# Power.net
KiCad netlist of a schematic drawn in Altium Designer
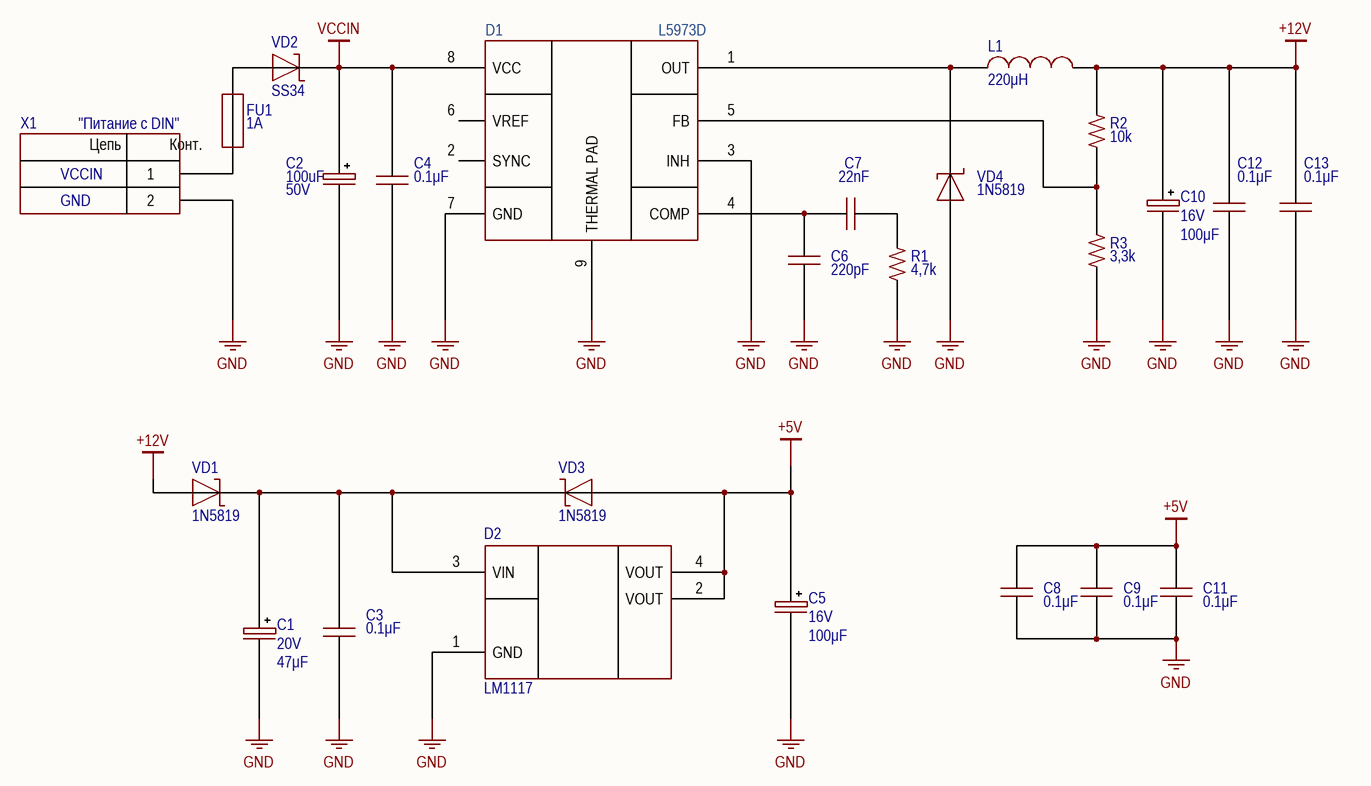
[diagram p0: Power.SchDoc]

(export (version "E")
  (design (tool "Eeschema 10.0.6"))
  (components
    (comp (ref "C1")
      (value "~")
      (footprint "Standart_Case:CAP: TANTAL-D")
      (fields (field (name "НАПРЯЖЕНИЕ") "20V") (field (name "ЗНАЧЕНИЕ") "47μF"))
      (libsource (lib "Capacitor") (part "Танталы SMD"))
    )
    (comp (ref "C2")
      (value "100uF")
      (footprint "Custom_Case:CAP: SMD D8A6.9")
      (fields
        (field (name "MANUFACTURER") "Capxon International Elec")
        (field (name "PARTNUMBER") "TH102M025I200ECAB")
        (field (name "VOLTAGE") "50V")
      )
      (libsource (lib "Capacitor") (part "Aluminium"))
    )
    (comp (ref "C3")
      (value "0.1μF")
      (footprint "Standart_Case:CAP: 0805")
      (fields
        (field (name "MANUFACTURER") "Murata Electronics")
        (field (name "PARTNUMBER") "GRM21BR71H104KA01L")
        (field (name "VALUEMANUFACTURERPARTNUMBER") "Керамический конденсатор, 0.1μF, X7R, ±10%, 16V, 0805, -55...+125°C")
      )
      (libsource (lib "Capacitor") (part "Ceramic_0805"))
    )
    (comp (ref "C4")
      (value "0.1μF")
      (footprint "Standart_Case:CAP: 0805")
      (fields
        (field (name "MANUFACTURER") "Murata Electronics")
        (field (name "PARTNUMBER") "GRM21BR71H104KA01L")
        (field (name "VALUEMANUFACTURERPARTNUMBER") "Керамический конденсатор, 0.1μF, X7R, ±10%, 50V, 0805, -55...+125°C")
      )
      (libsource (lib "Capacitor") (part "Ceramic_0805"))
    )
    (comp (ref "C5")
      (value "~")
      (footprint "Standart_Case:CAP: TANTAL-D")
      (fields (field (name "НАПРЯЖЕНИЕ") "16V") (field (name "ЗНАЧЕНИЕ") "100μF"))
      (libsource (lib "Capacitor") (part "Танталы SMD"))
    )
    (comp (ref "C6")
      (value "220pF")
      (footprint "Standart_Case:CAP: 0805")
      (fields
        (field (name "MANUFACTURER") "Murata Electronics")
        (field (name "PARTNUMBER") "GCJ21BR71H224KA01L")
        (field (name "VALUEMANUFACTURERPARTNUMBER") "Керамический конденсатор, 220pF, X7R, ±10%, 16V, 0805, -55...+125°C")
      )
      (libsource (lib "Capacitor") (part "Ceramic_0805"))
    )
    (comp (ref "C7")
      (value "22nF")
      (footprint "Standart_Case:CAP: 0805")
      (fields
        (field (name "MANUFACTURER") "Murata Electronics")
        (field (name "PARTNUMBER") "GCM216R71H223KA37D")
        (field (name "VALUEMANUFACTURERPARTNUMBER") "Керамический конденсатор, 22nF, X7R, ±10%, 16V, 0805, -55...+125°C")
      )
      (libsource (lib "Capacitor") (part "Ceramic_0805"))
    )
    (comp (ref "C8")
      (value "0.1μF")
      (footprint "Standart_Case:CAP: 0805")
      (fields
        (field (name "MANUFACTURER") "Murata Electronics")
        (field (name "PARTNUMBER") "GRM21BR71H104KA01L")
        (field (name "VALUEMANUFACTURERPARTNUMBER") "Керамический конденсатор, 0.1μF, X7R, ±10%, 16V, 0805, -55...+125°C")
      )
      (libsource (lib "Capacitor") (part "Ceramic_0805"))
    )
    (comp (ref "C9")
      (value "0.1μF")
      (footprint "Standart_Case:CAP: 0805")
      (fields
        (field (name "MANUFACTURER") "Murata Electronics")
        (field (name "PARTNUMBER") "GRM21BR71H104KA01L")
        (field (name "VALUEMANUFACTURERPARTNUMBER") "Керамический конденсатор, 0.1μF, X7R, ±10%, 16V, 0805, -55...+125°C")
      )
      (libsource (lib "Capacitor") (part "Ceramic_0805"))
    )
    (comp (ref "C10")
      (value "~")
      (footprint "Standart_Case:CAP: TANTAL-D")
      (fields (field (name "НАПРЯЖЕНИЕ") "16V") (field (name "ЗНАЧЕНИЕ") "100μF"))
      (libsource (lib "Capacitor") (part "Танталы SMD"))
    )
    (comp (ref "C11")
      (value "0.1μF")
      (footprint "Standart_Case:CAP: 0805")
      (fields
        (field (name "MANUFACTURER") "Murata Electronics")
        (field (name "PARTNUMBER") "GRM21BR71H104KA01L")
        (field (name "VALUEMANUFACTURERPARTNUMBER") "Керамический конденсатор, 0.1μF, X7R, ±10%, 16V, 0805, -55...+125°C")
      )
      (libsource (lib "Capacitor") (part "Ceramic_0805"))
    )
    (comp (ref "C12")
      (value "0.1μF")
      (footprint "Standart_Case:CAP: 0805")
      (fields
        (field (name "MANUFACTURER") "Murata Electronics")
        (field (name "PARTNUMBER") "GRM21BR71H104KA01L")
        (field (name "VALUEMANUFACTURERPARTNUMBER") "Керамический конденсатор, 0.1μF, X7R, ±10%, 16V, 0805, -55...+125°C")
      )
      (libsource (lib "Capacitor") (part "Ceramic_0805"))
    )
    (comp (ref "C13")
      (value "0.1μF")
      (footprint "Standart_Case:CAP: 0805")
      (fields
        (field (name "MANUFACTURER") "Murata Electronics")
        (field (name "PARTNUMBER") "GRM21BR71H104KA01L")
        (field (name "VALUEMANUFACTURERPARTNUMBER") "Керамический конденсатор, 0.1μF, X7R, ±10%, 16V, 0805, -55...+125°C")
      )
      (libsource (lib "Capacitor") (part "Ceramic_0805"))
    )
    (comp (ref "D1")
      (value "L5973D")
      (footprint "Standart_Case:HSOIC-DDA-8")
      (description "Импульсный понижающий регулятор напряжения")
      (fields (field (name "MANUFACTURER") "STMicroelectronics") (field (name "PARTNUMBER") "L5973D013TR"))
      (libsource (lib "IC_Power_Supply") (part "L5973D"))
    )
    (comp (ref "D2")
      (value "~")
      (footprint "Standart_Case:SOT223")
      (description "Линейный регулятор с низким падением напряжения")
      (fields (field (name "MANUFACTURER") "STMicroelectronics") (field (name "PARTNUMBER") "LM1117"))
      (libsource (lib "IC_Power_Supply") (part "LM1117"))
    )
    (comp (ref "FU1")
      (value "~")
      (footprint "Standart_case:FUSE: 1812")
      (fields
        (field (name "MANUFACTURER") "Littelfuse")
        (field (name "VALUEMANUFACTURERPARTNUMBER") "Предохранитель SMD, 250VAC, 1A, 1206, ")
        (field (name "PARTNUMBER") "0468001.NR")
        (field (name "MAXCURRENT") "1A")
      )
      (libsource (lib "Electromechanics") (part "Fuse"))
    )
    (comp (ref "L1")
      (value "220μH")
      (footprint "Custom_Case:IND: CD54")
      (fields
        (field (name "MANUFACTURER") "YJYCOIN")
        (field (name "PARTNUMBER") "CD54YP0504-221M")
        (field (name "VALUEMANUFACTURERPARTNUMBER") "Fixed inductor, 220μH, ±20%, CD54, 1.44A, -40...+100°C")
      )
      (libsource (lib "Inductor") (part "Inductor_CD54"))
    )
    (comp (ref "R1")
      (value "4,7k")
      (footprint "Standart_Case:RES: 0805")
      (fields
        (field (name "MANUFACTURER") "Vishay Intertech")
        (field (name "PARTNUMBER") "CRCW08054K70JNEA")
        (field (name "VALUEMANUFACTURERPARTNUMBER") "Резистор SMD, 4,7k, ±1%, 0805, 0.125W, -55...+125°C")
      )
      (libsource (lib "Resistor") (part "Resistor_0805_ieee"))
    )
    (comp (ref "R2")
      (value "10k")
      (footprint "Standart_Case:RES: 0805")
      (fields
        (field (name "MANUFACTURER") "Vishay Intertech")
        (field (name "PARTNUMBER") "CRCW080510K0FKEA")
        (field (name "VALUEMANUFACTURERPARTNUMBER") "Резистор SMD, 10k, ±1%, 0805, 0.125W, -55...+125°C")
      )
      (libsource (lib "Resistor") (part "Resistor_0805_ieee"))
    )
    (comp (ref "R3")
      (value "3,3k")
      (footprint "Standart_Case:RES: 0805")
      (fields
        (field (name "MANUFACTURER") "Vishay Intertech")
        (field (name "VALUEMANUFACTURERPARTNUMBER") "Резистор SMD, 3,3k, ±1%, 0805, 0.125W, -55...+125°C")
        (field (name "POWER") "0.125W")
      )
      (libsource (lib "Resistor") (part "Resistor_0805_ieee"))
    )
    (comp (ref "VD1")
      (value "~")
      (footprint "Standart_Case:DIODE: SOD123")
      (fields
        (field (name "MANUFACTURER") "BORN")
        (field (name "VALUEMANUFACTURERPARTNUMBER") "Диод Шоттки, 80V, 500mA, 1V, 15pF, SMA, -55...+150°C")
        (field (name "VOLTAGE") "80V")
        (field (name "PARTNUMBER") "1N5819")
      )
      (libsource (lib "Diode") (part "Schottky_single"))
    )
    (comp (ref "VD2")
      (value "~")
      (footprint "Standart_Case:DIODE: SMA")
      (fields
        (field (name "MANUFACTURER") "BORN")
        (field (name "VALUEMANUFACTURERPARTNUMBER") "Диод Шоттки, 80V, 500mA, 1V, 15pF, SMA, -55...+150°C")
        (field (name "VOLTAGE") "80V")
        (field (name "PARTNUMBER") "SS34")
      )
      (libsource (lib "Diode") (part "Schottky_single"))
    )
    (comp (ref "VD3")
      (value "~")
      (footprint "Standart_Case:DIODE: SOD123")
      (fields
        (field (name "MANUFACTURER") "BORN")
        (field (name "VALUEMANUFACTURERPARTNUMBER") "Диод Шоттки, 80V, 500mA, 1V, 15pF, SMA, -55...+150°C")
        (field (name "VOLTAGE") "80V")
        (field (name "PARTNUMBER") "1N5819")
      )
      (libsource (lib "Diode") (part "Schottky_single"))
    )
    (comp (ref "VD4")
      (value "~")
      (footprint "Standart_Case:DIODE: SOD123")
      (fields
        (field (name "MANUFACTURER") "Diodes Incorporated")
        (field (name "VALUEMANUFACTURERPARTNUMBER") "Диод Шоттки, 80V, 500mA, 1V, 15pF, SOD-123, -55...+150°C")
        (field (name "VOLTAGE") "80V")
        (field (name "PARTNUMBER") "1N5819")
      )
      (libsource (lib "Diode") (part "Schottky_single"))
    )
    (comp (ref "X1")
      (value "~")
      (footprint "Custom_Case:CON: 15EDGVC-3.5-02 (or 691321100002)")
      (fields
        (field (name "MANUFACTURER") "DEGSON")
        (field (name "VALUEMANUFACTURERPARTNUMBER") "Клеммник, 2pin, 3.5mm, 300VAC, 10A")
        (field (name "PARTNUMBER") "DG350-3.5-02P-14-00A(H)")
        (field (name "COMMENTTEXT") "\"Питание с DIN\"")
      )
      (libsource (lib "Connector") (part "Connector_terminal_2pin"))
    )
  )
  (nets
    (net (code "1") (name "+5V") (class "Default")
      (node (ref "C11") (pin "2") (pinfunction "2_2") (pintype "passive"))
      (node (ref "C5") (pin "1") (pinfunction "1_1") (pintype "passive"))
      (node (ref "C8") (pin "2") (pinfunction "2_2") (pintype "passive"))
      (node (ref "C9") (pin "2") (pinfunction "2_2") (pintype "passive"))
      (node (ref "D2") (pin "2") (pinfunction "VOUT_2") (pintype "power_in"))
      (node (ref "D2") (pin "4") (pinfunction "VOUT_4") (pintype "power_in"))
      (node (ref "VD3") (pin "1") (pinfunction "1_1") (pintype "passive"))
    )
    (net (code "2") (name "+12V") (class "Default")
      (node (ref "C10") (pin "1") (pinfunction "1_1") (pintype "passive"))
      (node (ref "C12") (pin "2") (pinfunction "2_2") (pintype "passive"))
      (node (ref "C13") (pin "2") (pinfunction "2_2") (pintype "passive"))
      (node (ref "L1") (pin "1") (pinfunction "1_1") (pintype "passive"))
      (node (ref "R2") (pin "1") (pinfunction "1_1") (pintype "passive"))
      (node (ref "VD1") (pin "1") (pinfunction "1_1") (pintype "passive"))
    )
    (net (code "3") (name "GND") (class "Default")
      (node (ref "C1") (pin "2") (pinfunction "2_2") (pintype "passive"))
      (node (ref "C10") (pin "2") (pinfunction "2_2") (pintype "passive"))
      (node (ref "C11") (pin "1") (pinfunction "1_1") (pintype "passive"))
      (node (ref "C12") (pin "1") (pinfunction "1_1") (pintype "passive"))
      (node (ref "C13") (pin "1") (pinfunction "1_1") (pintype "passive"))
      (node (ref "C2") (pin "2") (pinfunction "2_2") (pintype "passive"))
      (node (ref "C3") (pin "1") (pinfunction "1_1") (pintype "passive"))
      (node (ref "C4") (pin "1") (pinfunction "1_1") (pintype "passive"))
      (node (ref "C5") (pin "2") (pinfunction "2_2") (pintype "passive"))
      (node (ref "C6") (pin "2") (pinfunction "2_2") (pintype "passive"))
      (node (ref "C8") (pin "1") (pinfunction "1_1") (pintype "passive"))
      (node (ref "C9") (pin "1") (pinfunction "1_1") (pintype "passive"))
      (node (ref "D1") (pin "3") (pinfunction "INH_3") (pintype "passive"))
      (node (ref "D1") (pin "7") (pinfunction "GND_7") (pintype "passive"))
      (node (ref "D1") (pin "9") (pinfunction "THERMAL_PAD_9") (pintype "passive"))
      (node (ref "D2") (pin "1") (pinfunction "GND_1") (pintype "power_in"))
      (node (ref "R1") (pin "2") (pinfunction "2_2") (pintype "passive"))
      (node (ref "R3") (pin "2") (pinfunction "2_2") (pintype "passive"))
      (node (ref "VD4") (pin "1") (pinfunction "1_1") (pintype "passive"))
      (node (ref "X1") (pin "2") (pinfunction "2_2") (pintype "passive"))
    )
    (net (code "4") (name "Net-(C7-Pad1)") (class "Default")
      (node (ref "C7") (pin "1") (pinfunction "1_1") (pintype "passive"))
      (node (ref "R1") (pin "1") (pinfunction "1_1") (pintype "passive"))
    )
    (net (code "5") (name "Net-(D1-COMP)") (class "Default")
      (node (ref "C6") (pin "1") (pinfunction "1_1") (pintype "passive"))
      (node (ref "C7") (pin "2") (pinfunction "2_2") (pintype "passive"))
      (node (ref "D1") (pin "4") (pinfunction "COMP_4") (pintype "passive"))
    )
    (net (code "6") (name "Net-(D1-FB)") (class "Default")
      (node (ref "D1") (pin "5") (pinfunction "FB_5") (pintype "passive"))
      (node (ref "R2") (pin "2") (pinfunction "2_2") (pintype "passive"))
      (node (ref "R3") (pin "1") (pinfunction "1_1") (pintype "passive"))
    )
    (net (code "7") (name "Net-(D1-OUT)") (class "Default")
      (node (ref "D1") (pin "1") (pinfunction "OUT_1") (pintype "passive"))
      (node (ref "L1") (pin "2") (pinfunction "2_2") (pintype "passive"))
      (node (ref "VD4") (pin "2") (pinfunction "2_2") (pintype "passive"))
    )
    (net (code "8") (name "Net-(D2-VIN)") (class "Default")
      (node (ref "C1") (pin "1") (pinfunction "1_1") (pintype "passive"))
      (node (ref "C3") (pin "2") (pinfunction "2_2") (pintype "passive"))
      (node (ref "D2") (pin "3") (pinfunction "VIN_3") (pintype "power_in"))
      (node (ref "VD1") (pin "2") (pinfunction "2_2") (pintype "passive"))
      (node (ref "VD3") (pin "2") (pinfunction "2_2") (pintype "passive"))
    )
    (net (code "9") (name "Net-(FU1-Pad1)") (class "Default")
      (node (ref "FU1") (pin "1") (pinfunction "1_1") (pintype "passive"))
      (node (ref "X1") (pin "1") (pinfunction "1_1") (pintype "passive"))
    )
    (net (code "10") (name "Net-(FU1-Pad2)") (class "Default")
      (node (ref "FU1") (pin "2") (pinfunction "2_2") (pintype "passive"))
      (node (ref "VD2") (pin "1") (pinfunction "1_1") (pintype "passive"))
    )
    (net (code "11") (name "VCCIN") (class "Default")
      (node (ref "C2") (pin "1") (pinfunction "1_1") (pintype "passive"))
      (node (ref "C4") (pin "2") (pinfunction "2_2") (pintype "passive"))
      (node (ref "D1") (pin "8") (pinfunction "VCC_8") (pintype "passive"))
      (node (ref "VD2") (pin "2") (pinfunction "2_2") (pintype "passive"))
    )
    (net (code "12") (name "unconnected-(D1-SYNC-Pad2)") (class "Default")
      (node (ref "D1") (pin "2") (pinfunction "SYNC_2") (pintype "passive"))
    )
    (net (code "13") (name "unconnected-(D1-VREF-Pad6)") (class "Default")
      (node (ref "D1") (pin "6") (pinfunction "VREF_6") (pintype "passive"))
    )
  )
)
